# 6_-_CH340C.net
KiCad netlist of a schematic drawn in Altium Designer
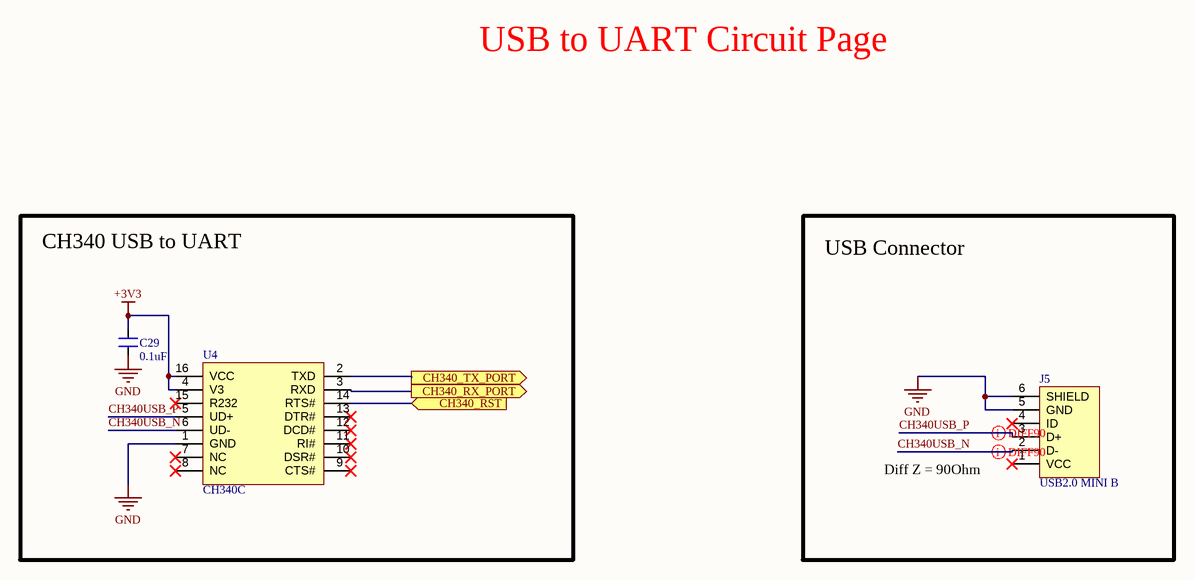
[diagram p0: [6] - CH340C.SchDoc]

(export (version "E")
  (design (tool "Eeschema 10.0.6"))
  (components
    (comp (ref "C29")
      (value "0.1uF")
      (footprint "CAP_0805")
      (description "0.1µF ±10% 50V Ceramic Capacitor X7R 0805 (2012 Metric)")
      (fields
        (field (name "MANUFACTURER") "Samsung")
        (field (name "MANUFACTURER PART NUMBER") "CL21B104KBCNNNC")
      )
      (libsource (lib "ESTEEMPCBLIB") (part "CAP_0.1uF-50V-10%-0805"))
    )
    (comp (ref "J5")
      (value "USB2.0 MINI B")
      (footprint "CON_690-005-299-043")
      (description "USB - mini B USB 2.0 Receptacle Connector 5 Position Surface Mount, Right Angle")
      (fields
        (field (name "MANUFACTURER") "EDAC")
        (field (name "MANUFACTURER PART NUMBER") "690-005-299-043")
      )
      (libsource (lib "ESTEEMPCBLIB") (part "CON_USB2.0-MINIB-SMD"))
    )
    (comp (ref "U4")
      (value "CH340C")
      (footprint "SOIC16_50_284_25X90_SMT")
      (description "USB Bridge, USB to UART USB 2.0 UART Interface")
      (fields (field (name "MANUFACTURER") "Olimex"))
      (libsource (lib "ESTEEMPCBLIB") (part "IC_CH340C"))
    )
  )
  (nets
    (net (code "1") (name "+3V3") (class "Default")
      (node (ref "C29") (pin "2") (pinfunction "2_2") (pintype "passive"))
      (node (ref "U4") (pin "16") (pinfunction "VCC_16") (pintype "passive"))
      (node (ref "U4") (pin "4") (pinfunction "V3_4") (pintype "passive"))
    )
    (net (code "2") (name "/CH340USB_N") (class "Default")
      (node (ref "J5") (pin "2") (pinfunction "D-_2") (pintype "passive"))
      (node (ref "U4") (pin "6") (pinfunction "UD-_6") (pintype "passive"))
    )
    (net (code "3") (name "/CH340USB_P") (class "Default")
      (node (ref "J5") (pin "3") (pinfunction "D+_3") (pintype "passive"))
      (node (ref "U4") (pin "5") (pinfunction "UD+_5") (pintype "passive"))
    )
    (net (code "4") (name "/CH340_RST") (class "Default")
      (node (ref "U4") (pin "14") (pinfunction "RTS#_14") (pintype "passive"))
    )
    (net (code "5") (name "/CH340_RX_PORT") (class "Default")
      (node (ref "U4") (pin "3") (pinfunction "RXD_3") (pintype "passive"))
    )
    (net (code "6") (name "/CH340_TX_PORT") (class "Default")
      (node (ref "U4") (pin "2") (pinfunction "TXD_2") (pintype "passive"))
    )
    (net (code "7") (name "GND") (class "Default")
      (node (ref "C29") (pin "1") (pinfunction "1_1") (pintype "passive"))
      (node (ref "J5") (pin "5") (pinfunction "GND_5") (pintype "passive"))
      (node (ref "J5") (pin "6") (pinfunction "SHIELD_6") (pintype "passive"))
      (node (ref "U4") (pin "1") (pinfunction "GND_1") (pintype "passive"))
    )
    (net (code "8") (name "unconnected-(J5-ID-Pad4)") (class "Default")
      (node (ref "J5") (pin "4") (pinfunction "ID_4") (pintype "passive+no_connect"))
    )
    (net (code "9") (name "unconnected-(J5-VCC-Pad1)") (class "Default")
      (node (ref "J5") (pin "1") (pinfunction "VCC_1") (pintype "passive+no_connect"))
    )
    (net (code "10") (name "unconnected-(U4-CTS#-Pad9)") (class "Default")
      (node (ref "U4") (pin "9") (pinfunction "CTS#_9") (pintype "passive+no_connect"))
    )
    (net (code "11") (name "unconnected-(U4-DCD#-Pad12)") (class "Default")
      (node (ref "U4") (pin "12") (pinfunction "DCD#_12") (pintype "passive+no_connect"))
    )
    (net (code "12") (name "unconnected-(U4-DSR#-Pad10)") (class "Default")
      (node (ref "U4") (pin "10") (pinfunction "DSR#_10") (pintype "passive+no_connect"))
    )
    (net (code "13") (name "unconnected-(U4-DTR#-Pad13)") (class "Default")
      (node (ref "U4") (pin "13") (pinfunction "DTR#_13") (pintype "passive+no_connect"))
    )
    (net (code "14") (name "unconnected-(U4-NC-Pad7)") (class "Default")
      (node (ref "U4") (pin "7") (pinfunction "NC_7") (pintype "passive+no_connect"))
    )
    (net (code "15") (name "unconnected-(U4-NC-Pad8)") (class "Default")
      (node (ref "U4") (pin "8") (pinfunction "NC_8") (pintype "passive+no_connect"))
    )
    (net (code "16") (name "unconnected-(U4-R232-Pad15)") (class "Default")
      (node (ref "U4") (pin "15") (pinfunction "R232_15") (pintype "passive+no_connect"))
    )
    (net (code "17") (name "unconnected-(U4-RI#-Pad11)") (class "Default")
      (node (ref "U4") (pin "11") (pinfunction "RI#_11") (pintype "passive+no_connect"))
    )
  )
)
